# Measure.net
KiCad netlist of a schematic drawn in Altium Designer
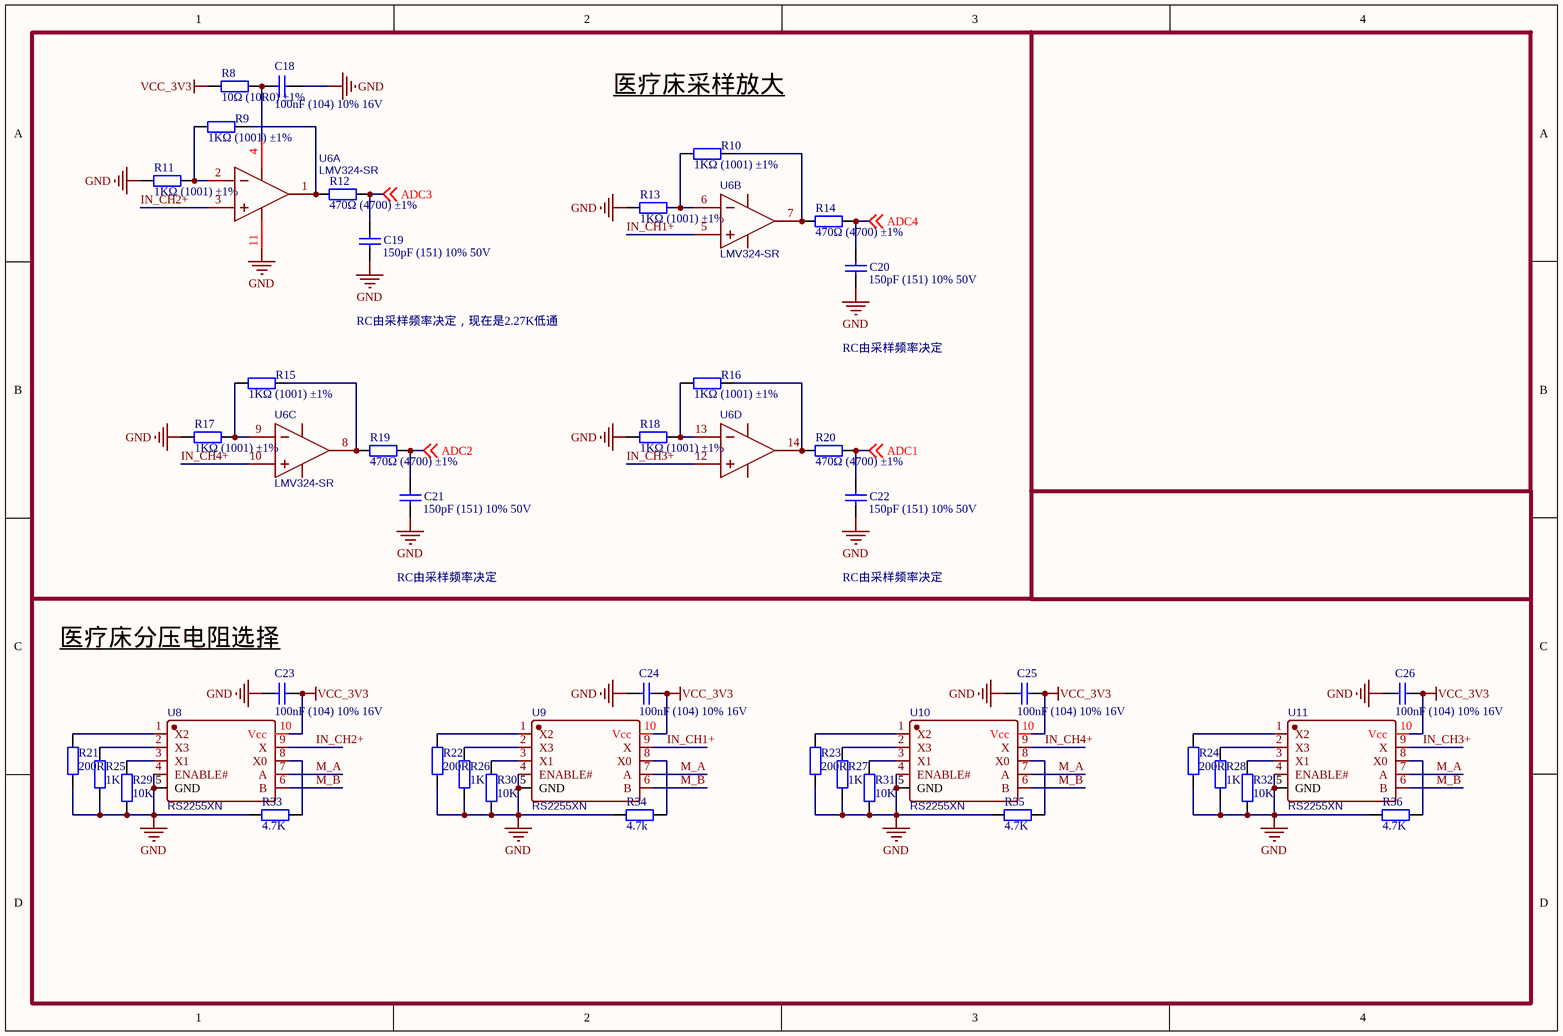
[diagram p0: Measure.SchDoc]

(export (version "E")
  (design (tool "Eeschema 10.0.6"))
  (components
    (comp (ref "C18")
      (value "100nF (104) 10% 16V")
      (footprint "0402_C")
      (description "贴片电容")
      (libsource (lib "Miscellaneous Devices LC") (part "0402 100nF (104) 10% 16V"))
    )
    (comp (ref "C19")
      (value "150pF (151) 10% 50V")
      (footprint "0402_C")
      (description "贴片电容")
      (libsource (lib "Miscellaneous Devices LC") (part "0402 150pF (151) 10% 50V"))
    )
    (comp (ref "C20")
      (value "150pF (151) 10% 50V")
      (footprint "0402_C")
      (description "贴片电容")
      (libsource (lib "Miscellaneous Devices LC") (part "0402 150pF (151) 10% 50V"))
    )
    (comp (ref "C21")
      (value "150pF (151) 10% 50V")
      (footprint "0402_C")
      (description "贴片电容")
      (libsource (lib "Miscellaneous Devices LC") (part "0402 150pF (151) 10% 50V"))
    )
    (comp (ref "C22")
      (value "150pF (151) 10% 50V")
      (footprint "0402_C")
      (description "贴片电容")
      (libsource (lib "Miscellaneous Devices LC") (part "0402 150pF (151) 10% 50V"))
    )
    (comp (ref "C23")
      (value "100nF (104) 10% 16V")
      (footprint "0402_C")
      (description "贴片电容")
      (libsource (lib "Miscellaneous Devices LC") (part "0402 100nF (104) 10% 16V"))
    )
    (comp (ref "C24")
      (value "100nF (104) 10% 16V")
      (footprint "0402_C")
      (description "贴片电容")
      (libsource (lib "Miscellaneous Devices LC") (part "0402 100nF (104) 10% 16V"))
    )
    (comp (ref "C25")
      (value "100nF (104) 10% 16V")
      (footprint "0402_C")
      (description "贴片电容")
      (libsource (lib "Miscellaneous Devices LC") (part "0402 100nF (104) 10% 16V"))
    )
    (comp (ref "C26")
      (value "100nF (104) 10% 16V")
      (footprint "0402_C")
      (description "贴片电容")
      (libsource (lib "Miscellaneous Devices LC") (part "0402 100nF (104) 10% 16V"))
    )
    (comp (ref "R8")
      (value "10Ω (10R0) ±1%")
      (footprint "0402_R")
      (description "贴片电阻")
      (libsource (lib "Miscellaneous Devices LC") (part "0402 10Ω (10R0) 1%"))
    )
    (comp (ref "R9")
      (value "1KΩ (1001) ±1%")
      (footprint "0402_R")
      (description "贴片电阻")
      (libsource (lib "Miscellaneous Devices LC") (part "0402 1KΩ (1001) 1%"))
    )
    (comp (ref "R10")
      (value "1KΩ (1001) ±1%")
      (footprint "0402_R")
      (description "贴片电阻")
      (libsource (lib "Miscellaneous Devices LC") (part "0402 1KΩ (1001) 1%"))
    )
    (comp (ref "R11")
      (value "1KΩ (1001) ±1%")
      (footprint "0402_R")
      (description "贴片电阻")
      (libsource (lib "Miscellaneous Devices LC") (part "0402 1KΩ (1001) 1%"))
    )
    (comp (ref "R12")
      (value "470Ω (4700) ±1%")
      (footprint "0402_R")
      (description "贴片电阻")
      (libsource (lib "Miscellaneous Devices LC") (part "0402 470Ω (4700) 1%"))
    )
    (comp (ref "R13")
      (value "1KΩ (1001) ±1%")
      (footprint "0402_R")
      (description "贴片电阻")
      (libsource (lib "Miscellaneous Devices LC") (part "0402 1KΩ (1001) 1%"))
    )
    (comp (ref "R14")
      (value "470Ω (4700) ±1%")
      (footprint "0402_R")
      (description "贴片电阻")
      (libsource (lib "Miscellaneous Devices LC") (part "0402 470Ω (4700) 1%"))
    )
    (comp (ref "R15")
      (value "1KΩ (1001) ±1%")
      (footprint "0402_R")
      (description "贴片电阻")
      (libsource (lib "Miscellaneous Devices LC") (part "0402 1KΩ (1001) 1%"))
    )
    (comp (ref "R16")
      (value "1KΩ (1001) ±1%")
      (footprint "0402_R")
      (description "贴片电阻")
      (libsource (lib "Miscellaneous Devices LC") (part "0402 1KΩ (1001) 1%"))
    )
    (comp (ref "R17")
      (value "1KΩ (1001) ±1%")
      (footprint "0402_R")
      (description "贴片电阻")
      (libsource (lib "Miscellaneous Devices LC") (part "0402 1KΩ (1001) 1%"))
    )
    (comp (ref "R18")
      (value "1KΩ (1001) ±1%")
      (footprint "0402_R")
      (description "贴片电阻")
      (libsource (lib "Miscellaneous Devices LC") (part "0402 1KΩ (1001) 1%"))
    )
    (comp (ref "R19")
      (value "470Ω (4700) ±1%")
      (footprint "0402_R")
      (description "贴片电阻")
      (libsource (lib "Miscellaneous Devices LC") (part "0402 470Ω (4700) 1%"))
    )
    (comp (ref "R20")
      (value "470Ω (4700) ±1%")
      (footprint "0402_R")
      (description "贴片电阻")
      (libsource (lib "Miscellaneous Devices LC") (part "0402 470Ω (4700) 1%"))
    )
    (comp (ref "R21")
      (value "200R")
      (footprint "0402_R")
      (description "贴片电阻")
      (libsource (lib "医疗床PCB") (part "0402 200Ω (2000) 1%"))
    )
    (comp (ref "R22")
      (value "200R")
      (footprint "0402_R")
      (description "贴片电阻")
      (libsource (lib "医疗床PCB") (part "0402 200Ω (2000) 1%"))
    )
    (comp (ref "R23")
      (value "200R")
      (footprint "0402_R")
      (description "贴片电阻")
      (libsource (lib "医疗床PCB") (part "0402 200Ω (2000) 1%"))
    )
    (comp (ref "R24")
      (value "200R")
      (footprint "0402_R")
      (description "贴片电阻")
      (libsource (lib "医疗床PCB") (part "0402 200Ω (2000) 1%"))
    )
    (comp (ref "R25")
      (value "1K")
      (footprint "0402_R")
      (description "贴片电阻")
      (libsource (lib "医疗床PCB") (part "0402 1KΩ (1001) 1%"))
    )
    (comp (ref "R26")
      (value "1K")
      (footprint "0402_R")
      (description "贴片电阻")
      (libsource (lib "医疗床PCB") (part "0402 1KΩ (1001) 1%"))
    )
    (comp (ref "R27")
      (value "1K")
      (footprint "0402_R")
      (description "贴片电阻")
      (libsource (lib "医疗床PCB") (part "0402 1KΩ (1001) 1%"))
    )
    (comp (ref "R28")
      (value "1K")
      (footprint "0402_R")
      (description "贴片电阻")
      (libsource (lib "医疗床PCB") (part "0402 1KΩ (1001) 1%"))
    )
    (comp (ref "R29")
      (value "10K")
      (footprint "0402_R")
      (description "贴片电阻")
      (libsource (lib "医疗床PCB") (part "0402 10KΩ (1002) 1%"))
    )
    (comp (ref "R30")
      (value "10K")
      (footprint "0402_R")
      (description "贴片电阻")
      (libsource (lib "医疗床PCB") (part "0402 10KΩ (1002) 1%"))
    )
    (comp (ref "R31")
      (value "10K")
      (footprint "0402_R")
      (description "贴片电阻")
      (libsource (lib "医疗床PCB") (part "0402 10KΩ (1002) 1%"))
    )
    (comp (ref "R32")
      (value "10K")
      (footprint "0402_R")
      (description "贴片电阻")
      (libsource (lib "医疗床PCB") (part "0402 10KΩ (1002) 1%"))
    )
    (comp (ref "R33")
      (value "4.7K")
      (footprint "0402_R")
      (description "贴片电阻")
      (libsource (lib "医疗床PCB") (part "0402 4.7KΩ (4701) 1%"))
    )
    (comp (ref "R34")
      (value "4.7k")
      (footprint "0402_R")
      (description "贴片电阻")
      (libsource (lib "医疗床PCB") (part "0402 4.7KΩ (4701) 1%"))
    )
    (comp (ref "R35")
      (value "4.7K")
      (footprint "0402_R")
      (description "贴片电阻")
      (libsource (lib "医疗床PCB") (part "0402 4.7KΩ (4701) 1%"))
    )
    (comp (ref "R36")
      (value "4.7K")
      (footprint "0402_R")
      (description "贴片电阻")
      (libsource (lib "医疗床PCB") (part "0402 4.7KΩ (4701) 1%"))
    )
    (comp (ref "U6")
      (value "LMV324-SR")
      (footprint "SOP-14_L8.6-W3.9-P1.27-LS6.0-BL")
      (fields
        (field (name "BOM_SUPPLIER PART") "C395458")
        (field (name "BOM_MANUFACTURER PART") "LMV324")
        (field (name "SUBPART_NO") "3")
      )
      (libsource (lib "医疗床PCB") (part "LMV324-SR"))
    )
    (comp (ref "U8")
      (value "RS2255XN")
      (footprint "MSOP-10_L3.0-W3.0-P0.50-LS5.0-BL")
      (fields (field (name "BOM_SUPPLIER PART") "C783421") (field (name "CONTRIBUTOR") "LCSC"))
      (libsource (lib "PCB_Bottom") (part "RS2255XN"))
    )
    (comp (ref "U9")
      (value "RS2255XN")
      (footprint "MSOP-10_L3.0-W3.0-P0.50-LS5.0-BL")
      (fields (field (name "BOM_SUPPLIER PART") "C783421") (field (name "CONTRIBUTOR") "LCSC"))
      (libsource (lib "PCB_Bottom") (part "RS2255XN"))
    )
    (comp (ref "U10")
      (value "RS2255XN")
      (footprint "MSOP-10_L3.0-W3.0-P0.50-LS5.0-BL")
      (fields (field (name "BOM_SUPPLIER PART") "C783421") (field (name "CONTRIBUTOR") "LCSC"))
      (libsource (lib "PCB_Bottom") (part "RS2255XN"))
    )
    (comp (ref "U11")
      (value "RS2255XN")
      (footprint "MSOP-10_L3.0-W3.0-P0.50-LS5.0-BL")
      (fields (field (name "BOM_SUPPLIER PART") "C783421") (field (name "CONTRIBUTOR") "LCSC"))
      (libsource (lib "PCB_Bottom") (part "RS2255XN"))
    )
  )
  (nets
    (net (code "1") (name "/IN_CH1+") (class "Default")
      (node (ref "U6") (pin "5") (pinfunction "2IN+_5") (pintype "passive"))
      (node (ref "U9") (pin "9") (pinfunction "X_9") (pintype "passive"))
    )
    (net (code "2") (name "/IN_CH2+") (class "Default")
      (node (ref "U6") (pin "3") (pinfunction "1IN+_3") (pintype "passive"))
      (node (ref "U8") (pin "9") (pinfunction "X_9") (pintype "passive"))
    )
    (net (code "3") (name "/IN_CH3+") (class "Default")
      (node (ref "U11") (pin "9") (pinfunction "X_9") (pintype "passive"))
      (node (ref "U6") (pin "12") (pinfunction "4IN+_12") (pintype "passive"))
    )
    (net (code "4") (name "/IN_CH4+") (class "Default")
      (node (ref "U10") (pin "9") (pinfunction "X_9") (pintype "passive"))
      (node (ref "U6") (pin "10") (pinfunction "3IN+_10") (pintype "passive"))
    )
    (net (code "5") (name "/M_A") (class "Default")
      (node (ref "U10") (pin "7") (pinfunction "A_7") (pintype "passive"))
      (node (ref "U11") (pin "7") (pinfunction "A_7") (pintype "passive"))
      (node (ref "U8") (pin "7") (pinfunction "A_7") (pintype "passive"))
      (node (ref "U9") (pin "7") (pinfunction "A_7") (pintype "passive"))
    )
    (net (code "6") (name "/M_B") (class "Default")
      (node (ref "U10") (pin "6") (pinfunction "B_6") (pintype "passive"))
      (node (ref "U11") (pin "6") (pinfunction "B_6") (pintype "passive"))
      (node (ref "U8") (pin "6") (pinfunction "B_6") (pintype "passive"))
      (node (ref "U9") (pin "6") (pinfunction "B_6") (pintype "passive"))
    )
    (net (code "7") (name "ADC1") (class "Default")
      (node (ref "C22") (pin "2") (pinfunction "2_2") (pintype "passive"))
      (node (ref "R20") (pin "2") (pinfunction "2_2") (pintype "passive"))
    )
    (net (code "8") (name "ADC2") (class "Default")
      (node (ref "C21") (pin "2") (pinfunction "2_2") (pintype "passive"))
      (node (ref "R19") (pin "2") (pinfunction "2_2") (pintype "passive"))
    )
    (net (code "9") (name "ADC3") (class "Default")
      (node (ref "C19") (pin "2") (pinfunction "2_2") (pintype "passive"))
      (node (ref "R12") (pin "2") (pinfunction "2_2") (pintype "passive"))
    )
    (net (code "10") (name "ADC4") (class "Default")
      (node (ref "C20") (pin "2") (pinfunction "2_2") (pintype "passive"))
      (node (ref "R14") (pin "2") (pinfunction "2_2") (pintype "passive"))
    )
    (net (code "11") (name "GND") (class "Default")
      (node (ref "C18") (pin "2") (pinfunction "2_2") (pintype "passive"))
      (node (ref "C19") (pin "1") (pinfunction "1_1") (pintype "passive"))
      (node (ref "C20") (pin "1") (pinfunction "1_1") (pintype "passive"))
      (node (ref "C21") (pin "1") (pinfunction "1_1") (pintype "passive"))
      (node (ref "C22") (pin "1") (pinfunction "1_1") (pintype "passive"))
      (node (ref "C23") (pin "2") (pinfunction "2_2") (pintype "passive"))
      (node (ref "C24") (pin "2") (pinfunction "2_2") (pintype "passive"))
      (node (ref "C25") (pin "2") (pinfunction "2_2") (pintype "passive"))
      (node (ref "C26") (pin "2") (pinfunction "2_2") (pintype "passive"))
      (node (ref "R11") (pin "1") (pinfunction "1_1") (pintype "passive"))
      (node (ref "R13") (pin "1") (pinfunction "1_1") (pintype "passive"))
      (node (ref "R17") (pin "1") (pinfunction "1_1") (pintype "passive"))
      (node (ref "R18") (pin "1") (pinfunction "1_1") (pintype "passive"))
      (node (ref "R21") (pin "1") (pinfunction "1_1") (pintype "passive"))
      (node (ref "R22") (pin "1") (pinfunction "1_1") (pintype "passive"))
      (node (ref "R23") (pin "1") (pinfunction "1_1") (pintype "passive"))
      (node (ref "R24") (pin "1") (pinfunction "1_1") (pintype "passive"))
      (node (ref "R25") (pin "2") (pinfunction "2_2") (pintype "passive"))
      (node (ref "R26") (pin "2") (pinfunction "2_2") (pintype "passive"))
      (node (ref "R27") (pin "2") (pinfunction "2_2") (pintype "passive"))
      (node (ref "R28") (pin "2") (pinfunction "2_2") (pintype "passive"))
      (node (ref "R29") (pin "2") (pinfunction "2_2") (pintype "passive"))
      (node (ref "R30") (pin "2") (pinfunction "2_2") (pintype "passive"))
      (node (ref "R31") (pin "2") (pinfunction "2_2") (pintype "passive"))
      (node (ref "R32") (pin "2") (pinfunction "2_2") (pintype "passive"))
      (node (ref "R33") (pin "2") (pinfunction "2_2") (pintype "passive"))
      (node (ref "R34") (pin "2") (pinfunction "2_2") (pintype "passive"))
      (node (ref "R35") (pin "2") (pinfunction "2_2") (pintype "passive"))
      (node (ref "R36") (pin "2") (pinfunction "2_2") (pintype "passive"))
      (node (ref "U10") (pin "4") (pinfunction "ENABLE#_4") (pintype "passive"))
      (node (ref "U10") (pin "5") (pinfunction "GND_5") (pintype "passive"))
      (node (ref "U11") (pin "4") (pinfunction "ENABLE#_4") (pintype "passive"))
      (node (ref "U11") (pin "5") (pinfunction "GND_5") (pintype "passive"))
      (node (ref "U6") (pin "11") (pinfunction "GND_11") (pintype "passive"))
      (node (ref "U8") (pin "4") (pinfunction "ENABLE#_4") (pintype "passive"))
      (node (ref "U8") (pin "5") (pinfunction "GND_5") (pintype "passive"))
      (node (ref "U9") (pin "4") (pinfunction "ENABLE#_4") (pintype "passive"))
      (node (ref "U9") (pin "5") (pinfunction "GND_5") (pintype "passive"))
    )
    (net (code "12") (name "Net-(U6A-1IN-)") (class "Default")
      (node (ref "R11") (pin "2") (pinfunction "2_2") (pintype "passive"))
      (node (ref "R9") (pin "1") (pinfunction "1_1") (pintype "passive"))
      (node (ref "U6") (pin "2") (pinfunction "1IN-_2") (pintype "passive"))
    )
    (net (code "13") (name "Net-(U6A-1OUT)") (class "Default")
      (node (ref "R12") (pin "1") (pinfunction "1_1") (pintype "passive"))
      (node (ref "R9") (pin "2") (pinfunction "2_2") (pintype "passive"))
      (node (ref "U6") (pin "1") (pinfunction "1OUT_1") (pintype "passive"))
    )
    (net (code "14") (name "Net-(U6A-VCC)") (class "Default")
      (node (ref "C18") (pin "1") (pinfunction "1_1") (pintype "passive"))
      (node (ref "R8") (pin "2") (pinfunction "2_2") (pintype "passive"))
      (node (ref "U6") (pin "4") (pinfunction "VCC_4") (pintype "passive"))
    )
    (net (code "15") (name "Net-(U6B-2IN-)") (class "Default")
      (node (ref "R10") (pin "1") (pinfunction "1_1") (pintype "passive"))
      (node (ref "R13") (pin "2") (pinfunction "2_2") (pintype "passive"))
      (node (ref "U6") (pin "6") (pinfunction "2IN-_6") (pintype "passive"))
    )
    (net (code "16") (name "Net-(U6B-2OUT)") (class "Default")
      (node (ref "R10") (pin "2") (pinfunction "2_2") (pintype "passive"))
      (node (ref "R14") (pin "1") (pinfunction "1_1") (pintype "passive"))
      (node (ref "U6") (pin "7") (pinfunction "2OUT_7") (pintype "passive"))
    )
    (net (code "17") (name "Net-(U6C-3IN-)") (class "Default")
      (node (ref "R15") (pin "1") (pinfunction "1_1") (pintype "passive"))
      (node (ref "R17") (pin "2") (pinfunction "2_2") (pintype "passive"))
      (node (ref "U6") (pin "9") (pinfunction "3IN-_9") (pintype "passive"))
    )
    (net (code "18") (name "Net-(U6C-3OUT)") (class "Default")
      (node (ref "R15") (pin "2") (pinfunction "2_2") (pintype "passive"))
      (node (ref "R19") (pin "1") (pinfunction "1_1") (pintype "passive"))
      (node (ref "U6") (pin "8") (pinfunction "3OUT_8") (pintype "passive"))
    )
    (net (code "19") (name "Net-(U6D-4IN-)") (class "Default")
      (node (ref "R16") (pin "1") (pinfunction "1_1") (pintype "passive"))
      (node (ref "R18") (pin "2") (pinfunction "2_2") (pintype "passive"))
      (node (ref "U6") (pin "13") (pinfunction "4IN-_13") (pintype "passive"))
    )
    (net (code "20") (name "Net-(U6D-4OUT)") (class "Default")
      (node (ref "R16") (pin "2") (pinfunction "2_2") (pintype "passive"))
      (node (ref "R20") (pin "1") (pinfunction "1_1") (pintype "passive"))
      (node (ref "U6") (pin "14") (pinfunction "4OUT_14") (pintype "passive"))
    )
    (net (code "21") (name "Net-(U8-X0)") (class "Default")
      (node (ref "R33") (pin "1") (pinfunction "1_1") (pintype "passive"))
      (node (ref "U8") (pin "8") (pinfunction "X0_8") (pintype "passive"))
    )
    (net (code "22") (name "Net-(U8-X1)") (class "Default")
      (node (ref "R29") (pin "1") (pinfunction "1_1") (pintype "passive"))
      (node (ref "U8") (pin "3") (pinfunction "X1_3") (pintype "passive"))
    )
    (net (code "23") (name "Net-(U8-X2)") (class "Default")
      (node (ref "R21") (pin "2") (pinfunction "2_2") (pintype "passive"))
      (node (ref "U8") (pin "1") (pinfunction "X2_1") (pintype "passive"))
    )
    (net (code "24") (name "Net-(U8-X3)") (class "Default")
      (node (ref "R25") (pin "1") (pinfunction "1_1") (pintype "passive"))
      (node (ref "U8") (pin "2") (pinfunction "X3_2") (pintype "passive"))
    )
    (net (code "25") (name "Net-(U9-X0)") (class "Default")
      (node (ref "R34") (pin "1") (pinfunction "1_1") (pintype "passive"))
      (node (ref "U9") (pin "8") (pinfunction "X0_8") (pintype "passive"))
    )
    (net (code "26") (name "Net-(U9-X1)") (class "Default")
      (node (ref "R30") (pin "1") (pinfunction "1_1") (pintype "passive"))
      (node (ref "U9") (pin "3") (pinfunction "X1_3") (pintype "passive"))
    )
    (net (code "27") (name "Net-(U9-X2)") (class "Default")
      (node (ref "R22") (pin "2") (pinfunction "2_2") (pintype "passive"))
      (node (ref "U9") (pin "1") (pinfunction "X2_1") (pintype "passive"))
    )
    (net (code "28") (name "Net-(U9-X3)") (class "Default")
      (node (ref "R26") (pin "1") (pinfunction "1_1") (pintype "passive"))
      (node (ref "U9") (pin "2") (pinfunction "X3_2") (pintype "passive"))
    )
    (net (code "29") (name "Net-(U10-X0)") (class "Default")
      (node (ref "R35") (pin "1") (pinfunction "1_1") (pintype "passive"))
      (node (ref "U10") (pin "8") (pinfunction "X0_8") (pintype "passive"))
    )
    (net (code "30") (name "Net-(U10-X1)") (class "Default")
      (node (ref "R31") (pin "1") (pinfunction "1_1") (pintype "passive"))
      (node (ref "U10") (pin "3") (pinfunction "X1_3") (pintype "passive"))
    )
    (net (code "31") (name "Net-(U10-X2)") (class "Default")
      (node (ref "R23") (pin "2") (pinfunction "2_2") (pintype "passive"))
      (node (ref "U10") (pin "1") (pinfunction "X2_1") (pintype "passive"))
    )
    (net (code "32") (name "Net-(U10-X3)") (class "Default")
      (node (ref "R27") (pin "1") (pinfunction "1_1") (pintype "passive"))
      (node (ref "U10") (pin "2") (pinfunction "X3_2") (pintype "passive"))
    )
    (net (code "33") (name "Net-(U11-X0)") (class "Default")
      (node (ref "R36") (pin "1") (pinfunction "1_1") (pintype "passive"))
      (node (ref "U11") (pin "8") (pinfunction "X0_8") (pintype "passive"))
    )
    (net (code "34") (name "Net-(U11-X1)") (class "Default")
      (node (ref "R32") (pin "1") (pinfunction "1_1") (pintype "passive"))
      (node (ref "U11") (pin "3") (pinfunction "X1_3") (pintype "passive"))
    )
    (net (code "35") (name "Net-(U11-X2)") (class "Default")
      (node (ref "R24") (pin "2") (pinfunction "2_2") (pintype "passive"))
      (node (ref "U11") (pin "1") (pinfunction "X2_1") (pintype "passive"))
    )
    (net (code "36") (name "Net-(U11-X3)") (class "Default")
      (node (ref "R28") (pin "1") (pinfunction "1_1") (pintype "passive"))
      (node (ref "U11") (pin "2") (pinfunction "X3_2") (pintype "passive"))
    )
    (net (code "37") (name "VCC_3V3") (class "Default")
      (node (ref "C23") (pin "1") (pinfunction "1_1") (pintype "passive"))
      (node (ref "C24") (pin "1") (pinfunction "1_1") (pintype "passive"))
      (node (ref "C25") (pin "1") (pinfunction "1_1") (pintype "passive"))
      (node (ref "C26") (pin "1") (pinfunction "1_1") (pintype "passive"))
      (node (ref "R8") (pin "1") (pinfunction "1_1") (pintype "passive"))
      (node (ref "U10") (pin "10") (pinfunction "Vcc_10") (pintype "passive"))
      (node (ref "U11") (pin "10") (pinfunction "Vcc_10") (pintype "passive"))
      (node (ref "U8") (pin "10") (pinfunction "Vcc_10") (pintype "passive"))
      (node (ref "U9") (pin "10") (pinfunction "Vcc_10") (pintype "passive"))
    )
  )
)
